# 4ROBOTS_UI_v_1_1.net
KiCad netlist of a schematic drawn in EAGLE
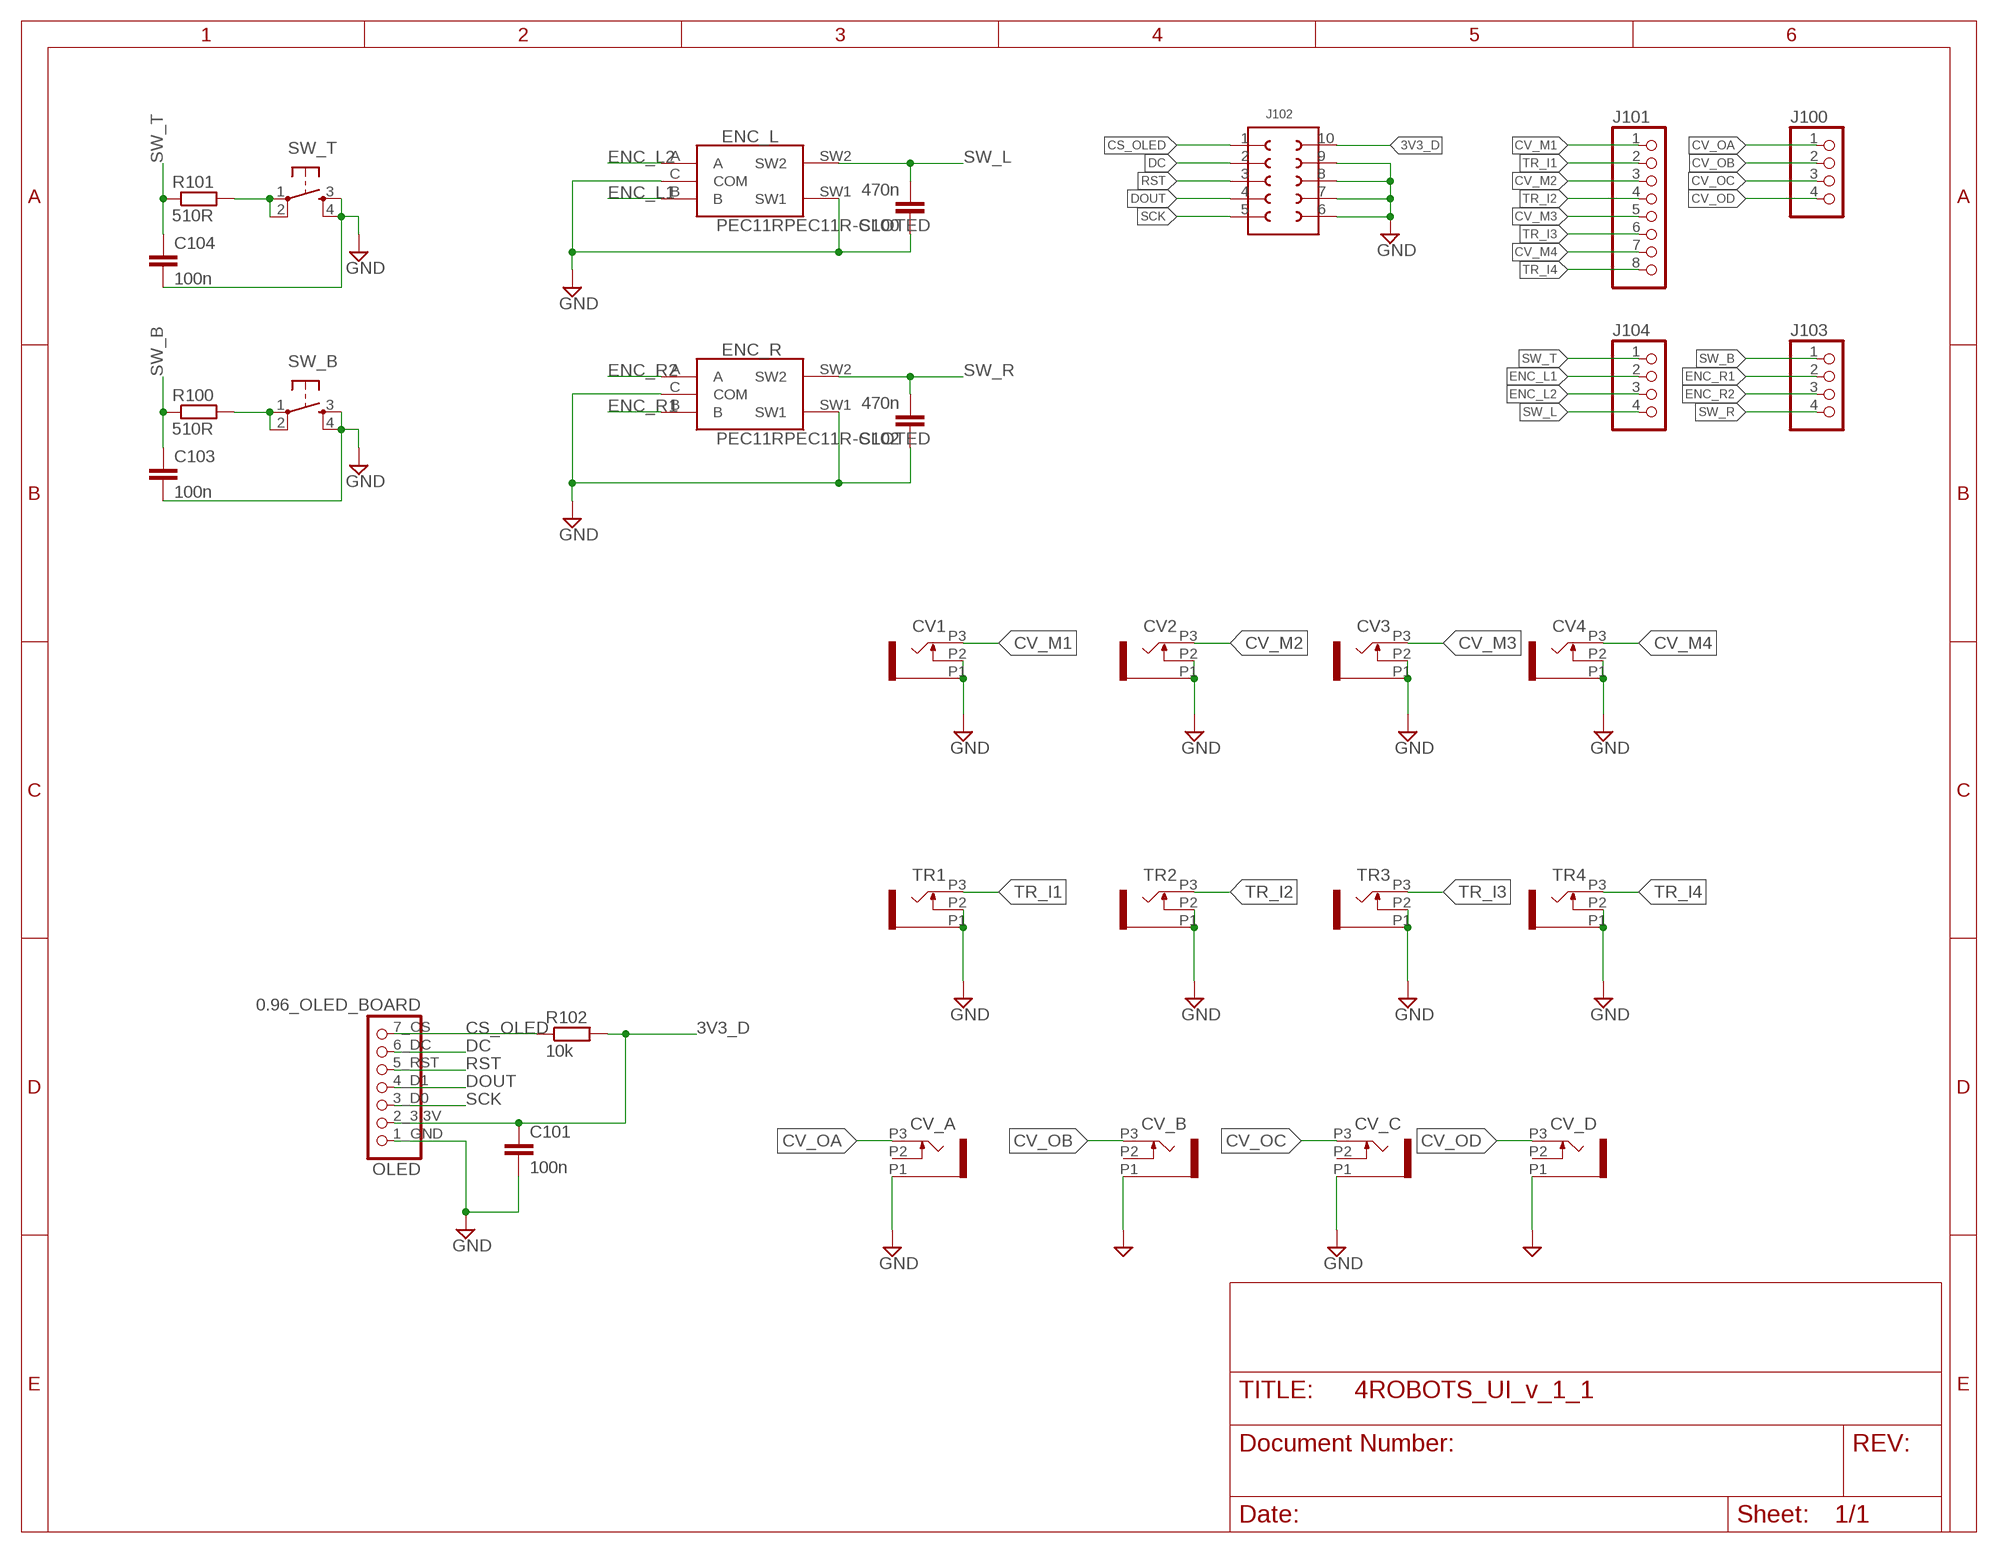
[diagram p0: schematic, sheet 1]

(export (version "E")
  (design (tool "Eeschema 10.0.6"))
  (components
    (comp (ref "C100")
      (value "470n")
      (footprint "eagle-import:C0603")
      (libsource (lib "eagle-import") (part "C-EUC0603"))
    )
    (comp (ref "C101")
      (value "100n")
      (footprint "eagle-import:C0603")
      (libsource (lib "eagle-import") (part "C-EUC0603"))
    )
    (comp (ref "C102")
      (value "470n")
      (footprint "eagle-import:C0603")
      (libsource (lib "eagle-import") (part "C-EUC0603"))
    )
    (comp (ref "C103")
      (value "100n")
      (footprint "eagle-import:C0603")
      (libsource (lib "eagle-import") (part "C-EUC0603"))
    )
    (comp (ref "C104")
      (value "100n")
      (footprint "eagle-import:C0603")
      (libsource (lib "eagle-import") (part "C-EUC0603"))
    )
    (comp (ref "CV1")
      (value "OG-PJ301_PJ301_THONKICONN6")
      (footprint "eagle-import:OG-PJ301_WQP_PJ_301M6")
      (libsource (lib "eagle-import") (part "OG-PJ301_PJ301_THONKICONN6"))
    )
    (comp (ref "CV2")
      (value "OG-PJ301_PJ301_THONKICONN6")
      (footprint "eagle-import:OG-PJ301_WQP_PJ_301M6")
      (libsource (lib "eagle-import") (part "OG-PJ301_PJ301_THONKICONN6"))
    )
    (comp (ref "CV3")
      (value "OG-PJ301_PJ301_THONKICONN6")
      (footprint "eagle-import:OG-PJ301_WQP_PJ_301M6")
      (libsource (lib "eagle-import") (part "OG-PJ301_PJ301_THONKICONN6"))
    )
    (comp (ref "CV4")
      (value "OG-PJ301_PJ301_THONKICONN6")
      (footprint "eagle-import:OG-PJ301_WQP_PJ_301M6")
      (libsource (lib "eagle-import") (part "OG-PJ301_PJ301_THONKICONN6"))
    )
    (comp (ref "CV_A")
      (value "OG-PJ301_PJ301_THONKICONN6")
      (footprint "eagle-import:OG-PJ301_WQP_PJ_301M6")
      (libsource (lib "eagle-import") (part "OG-PJ301_PJ301_THONKICONN6"))
    )
    (comp (ref "CV_B")
      (value "OG-PJ301_PJ301_THONKICONN6")
      (footprint "eagle-import:OG-PJ301_WQP_PJ_301M6")
      (libsource (lib "eagle-import") (part "OG-PJ301_PJ301_THONKICONN6"))
    )
    (comp (ref "CV_C")
      (value "OG-PJ301_PJ301_THONKICONN6")
      (footprint "eagle-import:OG-PJ301_WQP_PJ_301M6")
      (libsource (lib "eagle-import") (part "OG-PJ301_PJ301_THONKICONN6"))
    )
    (comp (ref "CV_D")
      (value "OG-PJ301_PJ301_THONKICONN6")
      (footprint "eagle-import:OG-PJ301_WQP_PJ_301M6")
      (libsource (lib "eagle-import") (part "OG-PJ301_PJ301_THONKICONN6"))
    )
    (comp (ref "ENC_L")
      (value "PEC11RPEC11R-SLOTED")
      (footprint "eagle-import:PEC11R-SLOTED")
      (libsource (lib "eagle-import") (part "PEC11RPEC11R-SLOTED"))
    )
    (comp (ref "ENC_R")
      (value "PEC11RPEC11R-SLOTED")
      (footprint "eagle-import:PEC11R-SLOTED")
      (libsource (lib "eagle-import") (part "PEC11RPEC11R-SLOTED"))
    )
    (comp (ref "J100")
      (value "PINHD-1X4")
      (footprint "eagle-import:1X04")
      (libsource (lib "eagle-import") (part "PINHD-1X4"))
    )
    (comp (ref "J101")
      (value "PINHD-1X8")
      (footprint "eagle-import:1X08")
      (libsource (lib "eagle-import") (part "PINHD-1X8"))
    )
    (comp (ref "J102")
      (value "61301021121")
      (footprint "eagle-import:61301021121")
      (libsource (lib "eagle-import") (part "61301021121"))
    )
    (comp (ref "J103")
      (value "PINHD-1X4")
      (footprint "eagle-import:1X04")
      (libsource (lib "eagle-import") (part "PINHD-1X4"))
    )
    (comp (ref "J104")
      (value "PINHD-1X4")
      (footprint "eagle-import:1X04")
      (libsource (lib "eagle-import") (part "PINHD-1X4"))
    )
    (comp (ref "OLED")
      (value "0.96_OLED_BOARD")
      (footprint "eagle-import:0.96_OLED_BOARD")
      (libsource (lib "eagle-import") (part "0.96_OLED_BOARD"))
    )
    (comp (ref "R100")
      (value "510R")
      (footprint "eagle-import:R0603")
      (libsource (lib "eagle-import") (part "R-EU_R0603"))
    )
    (comp (ref "R101")
      (value "510R")
      (footprint "eagle-import:R0603")
      (libsource (lib "eagle-import") (part "R-EU_R0603"))
    )
    (comp (ref "R102")
      (value "10k")
      (footprint "eagle-import:R0603")
      (libsource (lib "eagle-import") (part "R-EU_R0603"))
    )
    (comp (ref "SW_B")
      (value "TAC_SWITCHPTH")
      (footprint "eagle-import:TACTILE-PTH")
      (libsource (lib "eagle-import") (part "TAC_SWITCHPTH"))
    )
    (comp (ref "SW_T")
      (value "TAC_SWITCHPTH")
      (footprint "eagle-import:TACTILE-PTH")
      (libsource (lib "eagle-import") (part "TAC_SWITCHPTH"))
    )
    (comp (ref "TR1")
      (value "OG-PJ301_PJ301_THONKICONN6")
      (footprint "eagle-import:OG-PJ301_WQP_PJ_301M6")
      (libsource (lib "eagle-import") (part "OG-PJ301_PJ301_THONKICONN6"))
    )
    (comp (ref "TR2")
      (value "OG-PJ301_PJ301_THONKICONN6")
      (footprint "eagle-import:OG-PJ301_WQP_PJ_301M6")
      (libsource (lib "eagle-import") (part "OG-PJ301_PJ301_THONKICONN6"))
    )
    (comp (ref "TR3")
      (value "OG-PJ301_PJ301_THONKICONN6")
      (footprint "eagle-import:OG-PJ301_WQP_PJ_301M6")
      (libsource (lib "eagle-import") (part "OG-PJ301_PJ301_THONKICONN6"))
    )
    (comp (ref "TR4")
      (value "OG-PJ301_PJ301_THONKICONN6")
      (footprint "eagle-import:OG-PJ301_WQP_PJ_301M6")
      (libsource (lib "eagle-import") (part "OG-PJ301_PJ301_THONKICONN6"))
    )
  )
  (nets
    (net (code "1") (name "3V3_D") (class "Default")
      (node (ref "C101") (pin "1") (pinfunction "1_1") (pintype "passive"))
      (node (ref "J102") (pin "10") (pinfunction "10_10") (pintype "passive"))
      (node (ref "OLED") (pin "2_3.3V") (pinfunction "3V3_2_3.3V") (pintype "passive"))
      (node (ref "R102") (pin "2") (pinfunction "2_2") (pintype "passive"))
    )
    (net (code "2") (name "CS_OLED") (class "Default")
      (node (ref "J102") (pin "1") (pinfunction "1_1") (pintype "passive"))
      (node (ref "OLED") (pin "7_CS") (pinfunction "CS_7_CS") (pintype "passive"))
      (node (ref "R102") (pin "1") (pinfunction "1_1") (pintype "passive"))
    )
    (net (code "3") (name "CV_M1") (class "Default")
      (node (ref "CV1") (pin "P3") (pinfunction "3_P3") (pintype "passive"))
      (node (ref "J101") (pin "1") (pinfunction "1_1") (pintype "passive"))
    )
    (net (code "4") (name "CV_M2") (class "Default")
      (node (ref "CV2") (pin "P3") (pinfunction "3_P3") (pintype "passive"))
      (node (ref "J101") (pin "3") (pinfunction "3_3") (pintype "passive"))
    )
    (net (code "5") (name "CV_M3") (class "Default")
      (node (ref "CV3") (pin "P3") (pinfunction "3_P3") (pintype "passive"))
      (node (ref "J101") (pin "5") (pinfunction "5_5") (pintype "passive"))
    )
    (net (code "6") (name "CV_M4") (class "Default")
      (node (ref "CV4") (pin "P3") (pinfunction "3_P3") (pintype "passive"))
      (node (ref "J101") (pin "7") (pinfunction "7_7") (pintype "passive"))
    )
    (net (code "7") (name "CV_OA") (class "Default")
      (node (ref "CV_A") (pin "P3") (pinfunction "3_P3") (pintype "passive"))
      (node (ref "J100") (pin "1") (pinfunction "1_1") (pintype "passive"))
    )
    (net (code "8") (name "CV_OB") (class "Default")
      (node (ref "CV_B") (pin "P3") (pinfunction "3_P3") (pintype "passive"))
      (node (ref "J100") (pin "2") (pinfunction "2_2") (pintype "passive"))
    )
    (net (code "9") (name "CV_OC") (class "Default")
      (node (ref "CV_C") (pin "P3") (pinfunction "3_P3") (pintype "passive"))
      (node (ref "J100") (pin "3") (pinfunction "3_3") (pintype "passive"))
    )
    (net (code "10") (name "CV_OD") (class "Default")
      (node (ref "CV_D") (pin "P3") (pinfunction "3_P3") (pintype "passive"))
      (node (ref "J100") (pin "4") (pinfunction "4_4") (pintype "passive"))
    )
    (net (code "11") (name "DC") (class "Default")
      (node (ref "J102") (pin "2") (pinfunction "2_2") (pintype "passive"))
      (node (ref "OLED") (pin "6_DC") (pinfunction "DC_6_DC") (pintype "passive"))
    )
    (net (code "12") (name "DOUT") (class "Default")
      (node (ref "J102") (pin "4") (pinfunction "4_4") (pintype "passive"))
      (node (ref "OLED") (pin "4_D1") (pinfunction "D1_4_D1") (pintype "passive"))
    )
    (net (code "13") (name "ENC_L1") (class "Default")
      (node (ref "ENC_L") (pin "B") (pinfunction "B_B") (pintype "bidirectional"))
      (node (ref "J104") (pin "2") (pinfunction "2_2") (pintype "passive"))
    )
    (net (code "14") (name "ENC_L2") (class "Default")
      (node (ref "ENC_L") (pin "A") (pinfunction "A_A") (pintype "bidirectional"))
      (node (ref "J104") (pin "3") (pinfunction "3_3") (pintype "passive"))
    )
    (net (code "15") (name "ENC_R1") (class "Default")
      (node (ref "ENC_R") (pin "B") (pinfunction "B_B") (pintype "bidirectional"))
      (node (ref "J103") (pin "2") (pinfunction "2_2") (pintype "passive"))
    )
    (net (code "16") (name "ENC_R2") (class "Default")
      (node (ref "ENC_R") (pin "A") (pinfunction "A_A") (pintype "bidirectional"))
      (node (ref "J103") (pin "3") (pinfunction "3_3") (pintype "passive"))
    )
    (net (code "17") (name "GND") (class "Default")
      (node (ref "C100") (pin "1") (pinfunction "1_1") (pintype "passive"))
      (node (ref "C101") (pin "2") (pinfunction "2_2") (pintype "passive"))
      (node (ref "C102") (pin "1") (pinfunction "1_1") (pintype "passive"))
      (node (ref "C103") (pin "2") (pinfunction "2_2") (pintype "passive"))
      (node (ref "C104") (pin "2") (pinfunction "2_2") (pintype "passive"))
      (node (ref "CV1") (pin "P1") (pinfunction "1_P1") (pintype "passive"))
      (node (ref "CV1") (pin "P2") (pinfunction "2_P2") (pintype "passive"))
      (node (ref "CV2") (pin "P1") (pinfunction "1_P1") (pintype "passive"))
      (node (ref "CV2") (pin "P2") (pinfunction "2_P2") (pintype "passive"))
      (node (ref "CV3") (pin "P1") (pinfunction "1_P1") (pintype "passive"))
      (node (ref "CV3") (pin "P2") (pinfunction "2_P2") (pintype "passive"))
      (node (ref "CV4") (pin "P1") (pinfunction "1_P1") (pintype "passive"))
      (node (ref "CV4") (pin "P2") (pinfunction "2_P2") (pintype "passive"))
      (node (ref "CV_A") (pin "P1") (pinfunction "1_P1") (pintype "passive"))
      (node (ref "CV_B") (pin "P1") (pinfunction "1_P1") (pintype "passive"))
      (node (ref "CV_C") (pin "P1") (pinfunction "1_P1") (pintype "passive"))
      (node (ref "CV_D") (pin "P1") (pinfunction "1_P1") (pintype "passive"))
      (node (ref "ENC_L") (pin "C") (pinfunction "COM_C") (pintype "bidirectional"))
      (node (ref "ENC_L") (pin "SW1") (pinfunction "SW1_SW1") (pintype "bidirectional"))
      (node (ref "ENC_R") (pin "C") (pinfunction "COM_C") (pintype "bidirectional"))
      (node (ref "ENC_R") (pin "SW1") (pinfunction "SW1_SW1") (pintype "bidirectional"))
      (node (ref "J102") (pin "6") (pinfunction "6_6") (pintype "passive"))
      (node (ref "J102") (pin "7") (pinfunction "7_7") (pintype "passive"))
      (node (ref "J102") (pin "8") (pinfunction "8_8") (pintype "passive"))
      (node (ref "J102") (pin "9") (pinfunction "9_9") (pintype "passive"))
      (node (ref "OLED") (pin "1_GND") (pinfunction "GND_1_GND") (pintype "passive"))
      (node (ref "SW_B") (pin "3") (pinfunction "3_3") (pintype "passive"))
      (node (ref "SW_B") (pin "4") (pinfunction "4_4") (pintype "passive"))
      (node (ref "SW_T") (pin "3") (pinfunction "3_3") (pintype "passive"))
      (node (ref "SW_T") (pin "4") (pinfunction "4_4") (pintype "passive"))
      (node (ref "TR1") (pin "P1") (pinfunction "1_P1") (pintype "passive"))
      (node (ref "TR1") (pin "P2") (pinfunction "2_P2") (pintype "passive"))
      (node (ref "TR2") (pin "P1") (pinfunction "1_P1") (pintype "passive"))
      (node (ref "TR2") (pin "P2") (pinfunction "2_P2") (pintype "passive"))
      (node (ref "TR3") (pin "P1") (pinfunction "1_P1") (pintype "passive"))
      (node (ref "TR3") (pin "P2") (pinfunction "2_P2") (pintype "passive"))
      (node (ref "TR4") (pin "P1") (pinfunction "1_P1") (pintype "passive"))
      (node (ref "TR4") (pin "P2") (pinfunction "2_P2") (pintype "passive"))
    )
    (net (code "18") (name "Net-(R100-Pad2)") (class "Default")
      (node (ref "R100") (pin "2") (pinfunction "2_2") (pintype "passive"))
      (node (ref "SW_B") (pin "1") (pinfunction "1_1") (pintype "passive"))
      (node (ref "SW_B") (pin "2") (pinfunction "2_2") (pintype "passive"))
    )
    (net (code "19") (name "Net-(R101-Pad2)") (class "Default")
      (node (ref "R101") (pin "2") (pinfunction "2_2") (pintype "passive"))
      (node (ref "SW_T") (pin "1") (pinfunction "1_1") (pintype "passive"))
      (node (ref "SW_T") (pin "2") (pinfunction "2_2") (pintype "passive"))
    )
    (net (code "20") (name "RST") (class "Default")
      (node (ref "J102") (pin "3") (pinfunction "3_3") (pintype "passive"))
      (node (ref "OLED") (pin "5_RST") (pinfunction "RST_5_RST") (pintype "passive"))
    )
    (net (code "21") (name "SCK") (class "Default")
      (node (ref "J102") (pin "5") (pinfunction "5_5") (pintype "passive"))
      (node (ref "OLED") (pin "3_D0") (pinfunction "D0_3_D0") (pintype "passive"))
    )
    (net (code "22") (name "SW_B") (class "Default")
      (node (ref "C103") (pin "1") (pinfunction "1_1") (pintype "passive"))
      (node (ref "J103") (pin "1") (pinfunction "1_1") (pintype "passive"))
      (node (ref "R100") (pin "1") (pinfunction "1_1") (pintype "passive"))
    )
    (net (code "23") (name "SW_L") (class "Default")
      (node (ref "C100") (pin "2") (pinfunction "2_2") (pintype "passive"))
      (node (ref "ENC_L") (pin "SW2") (pinfunction "SW2_SW2") (pintype "bidirectional"))
      (node (ref "J104") (pin "4") (pinfunction "4_4") (pintype "passive"))
    )
    (net (code "24") (name "SW_R") (class "Default")
      (node (ref "C102") (pin "2") (pinfunction "2_2") (pintype "passive"))
      (node (ref "ENC_R") (pin "SW2") (pinfunction "SW2_SW2") (pintype "bidirectional"))
      (node (ref "J103") (pin "4") (pinfunction "4_4") (pintype "passive"))
    )
    (net (code "25") (name "SW_T") (class "Default")
      (node (ref "C104") (pin "1") (pinfunction "1_1") (pintype "passive"))
      (node (ref "J104") (pin "1") (pinfunction "1_1") (pintype "passive"))
      (node (ref "R101") (pin "1") (pinfunction "1_1") (pintype "passive"))
    )
    (net (code "26") (name "TR_I1") (class "Default")
      (node (ref "J101") (pin "2") (pinfunction "2_2") (pintype "passive"))
      (node (ref "TR1") (pin "P3") (pinfunction "3_P3") (pintype "passive"))
    )
    (net (code "27") (name "TR_I2") (class "Default")
      (node (ref "J101") (pin "4") (pinfunction "4_4") (pintype "passive"))
      (node (ref "TR2") (pin "P3") (pinfunction "3_P3") (pintype "passive"))
    )
    (net (code "28") (name "TR_I3") (class "Default")
      (node (ref "J101") (pin "6") (pinfunction "6_6") (pintype "passive"))
      (node (ref "TR3") (pin "P3") (pinfunction "3_P3") (pintype "passive"))
    )
    (net (code "29") (name "TR_I4") (class "Default")
      (node (ref "J101") (pin "8") (pinfunction "8_8") (pintype "passive"))
      (node (ref "TR4") (pin "P3") (pinfunction "3_P3") (pintype "passive"))
    )
    (net (code "30") (name "unconnected-(CV_A-2-PadP2)") (class "Default")
      (node (ref "CV_A") (pin "P2") (pinfunction "2_P2") (pintype "passive"))
    )
    (net (code "31") (name "unconnected-(CV_B-2-PadP2)") (class "Default")
      (node (ref "CV_B") (pin "P2") (pinfunction "2_P2") (pintype "passive"))
    )
    (net (code "32") (name "unconnected-(CV_C-2-PadP2)") (class "Default")
      (node (ref "CV_C") (pin "P2") (pinfunction "2_P2") (pintype "passive"))
    )
    (net (code "33") (name "unconnected-(CV_D-2-PadP2)") (class "Default")
      (node (ref "CV_D") (pin "P2") (pinfunction "2_P2") (pintype "passive"))
    )
  )
)
